# low-pass-filter.net
KiCad netlist of a schematic drawn in Altium Designer
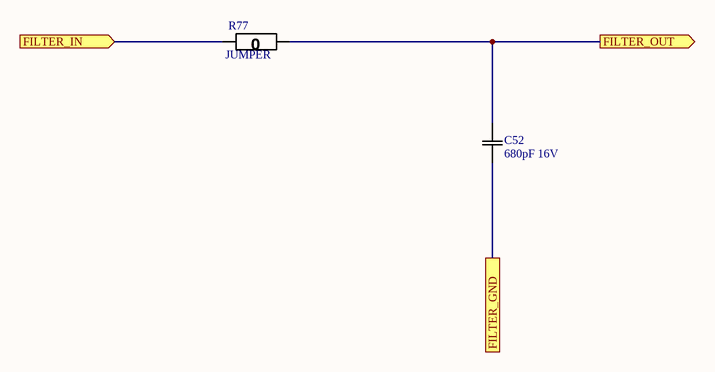
[diagram p0: low-pass-filter.SchDoc]

(export (version "E")
  (design (tool "Eeschema 10.0.6"))
  (components
    (comp (ref "C52")
      (value "680pF 16V")
      (footprint "0603")
      (description "Default Symbol for Capacitors")
      (fields (field (name "PART NUMBER") "CAP 680pF 16V") (field (name "TOLERANCE") "10%"))
      (libsource (lib "capacitor_library") (part "CAP_Default"))
    )
    (comp (ref "R77")
      (value "JUMPER")
      (footprint "0603")
      (description "RES SMD 0 OHM JUMPER GENERIC 0805")
      (fields (field (name "PART NUMBER") "RES 0 JUMPER"))
      (libsource (lib "Resistor_Library") (part "RES 0 JUMPER"))
    )
  )
  (nets
    (net (code "1") (name "/FILTER_GND") (class "Default")
      (node (ref "C52") (pin "1") (pinfunction "C1_1") (pintype "passive"))
    )
    (net (code "2") (name "/FILTER_IN") (class "Default")
      (node (ref "R77") (pin "2") (pinfunction "R2_2") (pintype "passive"))
    )
    (net (code "3") (name "/FILTER_OUT") (class "Default")
      (node (ref "C52") (pin "2") (pinfunction "C2_2") (pintype "passive"))
      (node (ref "R77") (pin "1") (pinfunction "R1_1") (pintype "passive"))
    )
  )
)
